# 3_mic.net
KiCad netlist of a schematic drawn in Altium Designer
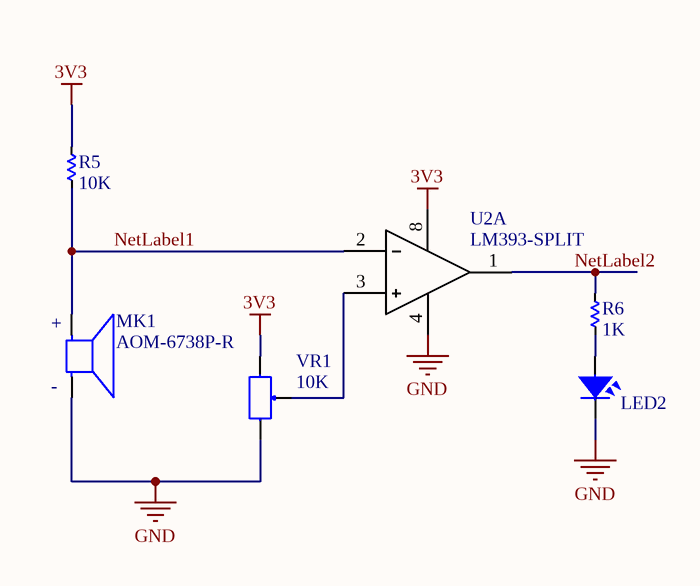
[diagram p0: [3]mic.SchDoc]

(export (version "E")
  (design (tool "Eeschema 10.0.6"))
  (components
    (comp (ref "LED2")
      (value "LED")
      (footprint "LED-0805-Green")
      (libsource (lib "LIBRARY") (part "LED SMD"))
    )
    (comp (ref "MK1")
      (value "AOM-6738P-R")
      (footprint "MIC_AOM-6738P-R:MIC_AOM-6738P-R")
      (description "MICROPHONE -38DB1.5VDC .5MA 2.2KOHM")
      (fields (field (name "MF") "PUI"))
      (libsource (lib "AOM-6738P-R") (part "AOM-6738P-R"))
    )
    (comp (ref "R5")
      (value "10K")
      (footprint "RES-SMD-0805")
      (description "Resistor")
      (fields
        (field (name "MANUFACTURER") "Generic Components")
        (field (name "PUBLISHER") "Altium Hobart Technology Centre")
      )
      (libsource (lib "LIBRARY") (part "Res-SMD"))
    )
    (comp (ref "R6")
      (value "1K")
      (footprint "RES-SMD-0805")
      (description "Resistor")
      (fields
        (field (name "MANUFACTURER") "Generic Components")
        (field (name "PUBLISHER") "Altium Hobart Technology Centre")
      )
      (libsource (lib "LIBRARY") (part "Res-SMD"))
    )
    (comp (ref "U2")
      (value "LM393-SPLIT")
      (footprint "SO8")
      (description "IC DUAL COMPARATOR")
      (libsource (lib "LIBRARY") (part "LM393-SPLIT"))
    )
    (comp (ref "VR1")
      (value "10K")
      (footprint "VR")
      (description "Var Resistor")
      (libsource (lib "LIBTanCN") (part "VR"))
    )
  )
  (nets
    (net (code "1") (name "/NetLabel1") (class "Default")
      (node (ref "MK1") (pin "P") (pinfunction "POS_P") (pintype "passive"))
      (node (ref "R5") (pin "2") (pinfunction "2_2") (pintype "passive"))
      (node (ref "U2") (pin "2") (pintype "passive"))
    )
    (net (code "2") (name "/NetLabel2") (class "Default")
      (node (ref "R6") (pin "1") (pinfunction "1_1") (pintype "passive"))
      (node (ref "U2") (pin "1") (pintype "passive"))
    )
    (net (code "3") (name "3V3") (class "Default")
      (node (ref "R5") (pin "1") (pinfunction "1_1") (pintype "passive"))
      (node (ref "U2") (pin "8") (pinfunction "Vcc+_8") (pintype "passive"))
      (node (ref "VR1") (pin "1") (pinfunction "1_1") (pintype "passive"))
    )
    (net (code "4") (name "GND") (class "Default")
      (node (ref "LED2") (pin "2") (pinfunction "2_2") (pintype "passive"))
      (node (ref "MK1") (pin "N") (pinfunction "NEG_N") (pintype "passive"))
      (node (ref "U2") (pin "4") (pinfunction "Vcc-_4") (pintype "passive"))
      (node (ref "VR1") (pin "3") (pinfunction "3_3") (pintype "passive"))
    )
    (net (code "5") (name "Net-(LED2-Pad1)") (class "Default")
      (node (ref "LED2") (pin "1") (pinfunction "1_1") (pintype "passive"))
      (node (ref "R6") (pin "2") (pinfunction "2_2") (pintype "passive"))
    )
    (net (code "6") (name "Net-(U2-Pad3)") (class "Default")
      (node (ref "U2") (pin "3") (pintype "passive"))
      (node (ref "VR1") (pin "2") (pinfunction "2_2") (pintype "passive"))
    )
  )
)
